# micro.net
KiCad netlist of a schematic drawn in Altium Designer
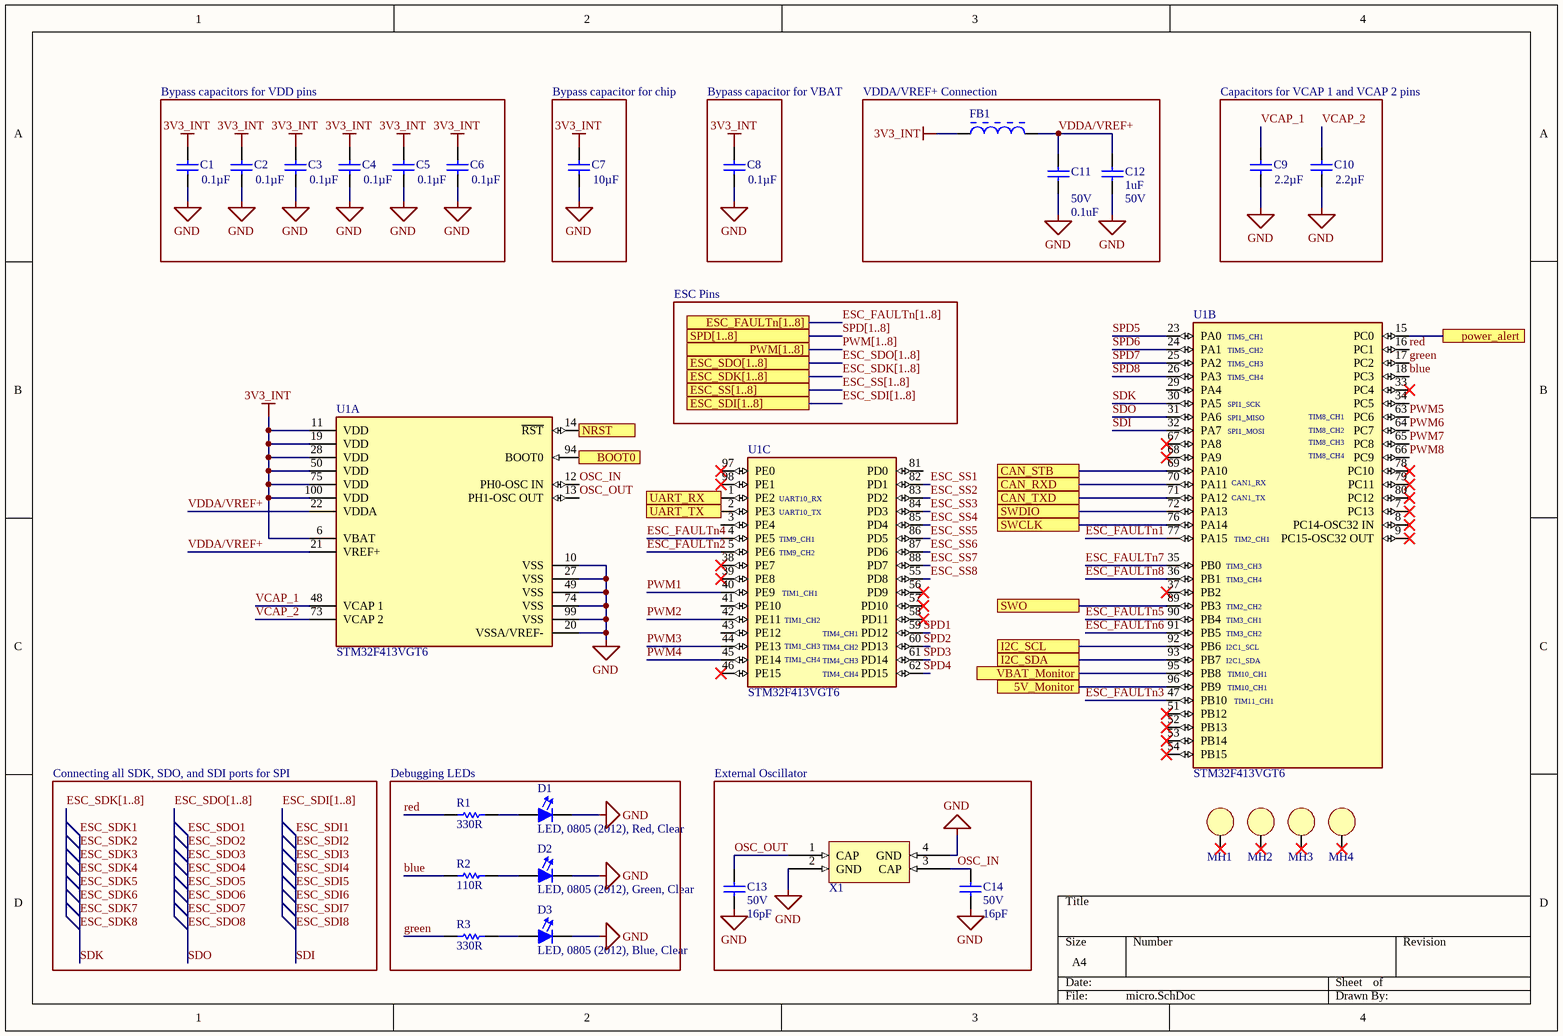
[diagram p0: micro.SchDoc]

(export (version "E")
  (design (tool "Eeschema 10.0.6"))
  (components
    (comp (ref "C1")
      (value "0.1µF")
      (footprint "CAPC1608N(0603\")")
      (description "Capacitor, Ceramic, 16V, +/- 10%, 0603 SMD, X7R")
      (fields
        (field (name "Comment") "0.1uF 16V 0603 SMD, Ceramic")
        (field (name "CREATED BY") "Andy Bates")
        (field (name "PUBLISHER") "AUVic")
      )
      (libsource (lib "") (part "Symbol_1"))
    )
    (comp (ref "C2")
      (value "0.1µF")
      (footprint "CAPC1608N(0603\")")
      (description "Capacitor, Ceramic, 16V, +/- 10%, 0603 SMD, X7R")
      (fields
        (field (name "Comment") "0.1uF 16V 0603 SMD, Ceramic")
        (field (name "CREATED BY") "Andy Bates")
        (field (name "PUBLISHER") "AUVic")
      )
      (libsource (lib "") (part "Symbol_1"))
    )
    (comp (ref "C3")
      (value "0.1µF")
      (footprint "CAPC1608N(0603\")")
      (description "Capacitor, Ceramic, 16V, +/- 10%, 0603 SMD, X7R")
      (fields
        (field (name "Comment") "0.1uF 16V 0603 SMD, Ceramic")
        (field (name "CREATED BY") "Andy Bates")
        (field (name "PUBLISHER") "AUVic")
      )
      (libsource (lib "") (part "Symbol_1"))
    )
    (comp (ref "C4")
      (value "0.1µF")
      (footprint "CAPC1608N(0603\")")
      (description "Capacitor, Ceramic, 16V, +/- 10%, 0603 SMD, X7R")
      (fields
        (field (name "Comment") "0.1uF 16V 0603 SMD, Ceramic")
        (field (name "CREATED BY") "Andy Bates")
        (field (name "PUBLISHER") "AUVic")
      )
      (libsource (lib "") (part "Symbol_1"))
    )
    (comp (ref "C5")
      (value "0.1µF")
      (footprint "CAPC1608N(0603\")")
      (description "Capacitor, Ceramic, 16V, +/- 10%, 0603 SMD, X7R")
      (fields
        (field (name "Comment") "0.1uF 16V 0603 SMD, Ceramic")
        (field (name "CREATED BY") "Andy Bates")
        (field (name "PUBLISHER") "AUVic")
      )
      (libsource (lib "") (part "Symbol_1"))
    )
    (comp (ref "C6")
      (value "0.1µF")
      (footprint "CAPC1608N(0603\")")
      (description "Capacitor, Ceramic, 16V, +/- 10%, 0603 SMD, X7R")
      (fields
        (field (name "Comment") "0.1uF 16V 0603 SMD, Ceramic")
        (field (name "CREATED BY") "Andy Bates")
        (field (name "PUBLISHER") "AUVic")
      )
      (libsource (lib "") (part "Symbol_1"))
    )
    (comp (ref "C7")
      (value "10µF")
      (footprint "CAPC2012N(0805\")")
      (description "Capacitor, Ceramic, 10V, +/- 10%, 0805 SMD, X5R")
      (fields
        (field (name "Comment") "10uF 10V 0805 SMD, Ceramic")
        (field (name "MADE BY") "Andy Bates")
        (field (name "PUBLISHER") "AUVic")
      )
      (libsource (lib "") (part "Symbol_3"))
    )
    (comp (ref "C8")
      (value "0.1µF")
      (footprint "CAPC1608N(0603\")")
      (description "Capacitor, Ceramic, 16V, +/- 10%, 0603 SMD, X7R")
      (fields
        (field (name "Comment") "0.1uF 16V 0603 SMD, Ceramic")
        (field (name "CREATED BY") "Andy Bates")
        (field (name "PUBLISHER") "AUVic")
      )
      (libsource (lib "") (part "Symbol_1"))
    )
    (comp (ref "C9")
      (value "2.2µF")
      (footprint "CAPC1608N(0603\")")
      (description "Capacitor, Ceramic, 50V, 10%, 0603 SMD, X5R")
      (fields
        (field (name "Comment") "2.2uF, 50V, 0603 SMD, X5R, Ceramic")
        (field (name "MADE BY") "*")
        (field (name "PUBLISHER") "AUVic")
      )
      (libsource (lib "") (part "Symbol_1"))
    )
    (comp (ref "C10")
      (value "2.2µF")
      (footprint "CAPC1608N(0603\")")
      (description "Capacitor, Ceramic, 50V, 10%, 0603 SMD, X5R")
      (fields
        (field (name "Comment") "2.2uF, 50V, 0603 SMD, X5R, Ceramic")
        (field (name "MADE BY") "*")
        (field (name "PUBLISHER") "AUVic")
      )
      (libsource (lib "") (part "Symbol_1"))
    )
    (comp (ref "C11")
      (value "CL10B104JB8NNNC")
      (footprint "FP-CL10-0_1-MFG")
      (description "CAP CER 0.1UF 50V X7R 0603")
      (fields
        (field (name "TOLERANCE") "5%")
        (field (name "VOLTAGE") "50V")
        (field (name "CAPACITANCE") "0.1uF")
      )
      (libsource (lib "AUVIC") (part "CAP-NP-2"))
    )
    (comp (ref "C12")
      (value "CL21B105KBFNNNG")
      (footprint "0803 CAP")
      (description "SAMSUNG ELECTRO-MECHANICS - CL21B105KBFNNNG - MLCC CAPACITORS")
      (fields
        (field (name "CAPACITANCE") "1uF")
        (field (name "TOLERANCE") "10%")
        (field (name "VOLTAGE") "50V")
      )
      (libsource (lib "") (part "Symbol_2"))
    )
    (comp (ref "C13")
      (value "16pF Ceramic 50V 5% 0603")
      (footprint "CAPC1608X90X35LL10T15")
      (description "Cap Ceramic 16pF 50V C0G 5% SMD 0603 125C Paper T/R")
      (fields
        (field (name "VOLTAGE") "50V")
        (field (name "TOLERANCE") "5%")
        (field (name "CAPACITANCE") "16pF")
      )
      (libsource (lib "AUVIC") (part "CAP"))
    )
    (comp (ref "C14")
      (value "16pF Ceramic 50V 5% 0603")
      (footprint "CAPC1608X90X35LL10T15")
      (description "Cap Ceramic 16pF 50V C0G 5% SMD 0603 125C Paper T/R")
      (fields
        (field (name "VOLTAGE") "50V")
        (field (name "TOLERANCE") "5%")
        (field (name "CAPACITANCE") "16pF")
      )
      (libsource (lib "AUVIC") (part "CAP"))
    )
    (comp (ref "D1")
      (value "LED, 0805 (2012), Red, Clear")
      (footprint "LED0805")
      (fields (field (name "CREATED BY") "Ashwin Sira"))
      (libsource (lib "AUVIC") (part "Symbol"))
    )
    (comp (ref "D2")
      (value "LED, 0805 (2012), Green, Clear")
      (footprint "LED0805")
      (fields (field (name "CREATED BY") "Andy Bates"))
      (libsource (lib "AUVIC") (part "Symbol"))
    )
    (comp (ref "D3")
      (value "LED, 0805 (2012), Blue, Clear")
      (footprint "LED0805")
      (fields (field (name "CREATED BY") "Ashwin Sira"))
      (libsource (lib "AUVIC") (part "Symbol"))
    )
    (comp (ref "FB1")
      (value "BLM18AG601SN1D")
      (footprint "MURA-BLM18-F-H1-CHIP-2_V")
      (fields (field (name "TOLERANCE") "25%"))
      (libsource (lib "AUVIC") (part "MURA-FB-2"))
    )
    (comp (ref "MH1")
      (value "Mount_Hole_3mm")
      (footprint "Mount-Hole_3mm")
      (description "Mounting hold for M3 hex standoff")
      (libsource (lib "AUVIC") (part "Mount_Hole_3mm"))
    )
    (comp (ref "MH2")
      (value "Mount_Hole_3mm")
      (footprint "Mount-Hole_3mm")
      (description "Mounting hold for M3 hex standoff")
      (libsource (lib "AUVIC") (part "Mount_Hole_3mm"))
    )
    (comp (ref "MH3")
      (value "Mount_Hole_3mm")
      (footprint "Mount-Hole_3mm")
      (description "Mounting hold for M3 hex standoff")
      (libsource (lib "AUVIC") (part "Mount_Hole_3mm"))
    )
    (comp (ref "MH4")
      (value "Mount_Hole_3mm")
      (footprint "Mount-Hole_3mm")
      (description "Mounting hold for M3 hex standoff")
      (libsource (lib "AUVIC") (part "Mount_Hole_3mm"))
    )
    (comp (ref "R1")
      (value "CRCW0603330RFKEA")
      (footprint "FP-CRCW0603-e3-IPC_C")
      (description "Res Thick Film 0603 330 Ohm 1% 0.1W(1/10W) +/-100ppm/ßC Pad SMD Automotive T/R")
      (fields (field (name "TOLERANCE") "1%") (field (name "RESISTANCE") "330R"))
      (libsource (lib "AUVIC") (part "RES"))
    )
    (comp (ref "R2")
      (value "RC0603FR-07110RL")
      (footprint "RESC1608X55X25ML10T15")
      (description "RES SMD 110 OHM 1% 1/10W 0603")
      (fields (field (name "TOLERANCE") "1%") (field (name "RESISTANCE") "110R"))
      (libsource (lib "AUVIC") (part "RES"))
    )
    (comp (ref "R3")
      (value "CRCW0603330RFKEA")
      (footprint "FP-CRCW0603-e3-IPC_C")
      (description "Res Thick Film 0603 330 Ohm 1% 0.1W(1/10W) +/-100ppm/ßC Pad SMD Automotive T/R")
      (fields (field (name "TOLERANCE") "1%") (field (name "RESISTANCE") "330R"))
      (libsource (lib "AUVIC") (part "RES"))
    )
    (comp (ref "U1")
      (value "STM32F413VGT6")
      (footprint "FP-LQFP100-1L-IPC_C")
      (description "IC MCU 32BIT 1MB FLASH 100LQFP")
      (libsource (lib "AUVIC") (part "38cd4fa6327843ddc5f699c16638a8b"))
    )
    (comp (ref "X1")
      (value "CRYSTAL 8.0MHZ 16PF SMD")
      (footprint "QFN250P750X520X140_HS-5M")
      (description "8MHz ±30ppm Crystal 16pF 80 Ohms 4-SMD, No Lead")
      (libsource (lib "AUVIC") (part "LFXTAL026380REEL"))
    )
  )
  (nets
    (net (code "1") (name "/5V_Monitor") (class "Default")
      (node (ref "U1") (pin "96") (pinfunction "PB9_96") (pintype "bidirectional"))
    )
    (net (code "2") (name "/BOOT0") (class "Default")
      (node (ref "U1") (pin "94") (pinfunction "BOOT0_94") (pintype "input"))
    )
    (net (code "3") (name "/CAN_RXD") (class "Default")
      (node (ref "U1") (pin "70") (pinfunction "PA11_70") (pintype "bidirectional"))
    )
    (net (code "4") (name "/CAN_STB") (class "Default")
      (node (ref "U1") (pin "69") (pinfunction "PA10_69") (pintype "bidirectional"))
    )
    (net (code "5") (name "/CAN_TXD") (class "Default")
      (node (ref "U1") (pin "71") (pinfunction "PA12_71") (pintype "bidirectional"))
    )
    (net (code "6") (name "/ESC_FAULTn1") (class "Default")
      (node (ref "U1") (pin "77") (pinfunction "PA15_77") (pintype "bidirectional"))
    )
    (net (code "7") (name "/ESC_FAULTn2") (class "Default")
      (node (ref "U1") (pin "5") (pinfunction "PE6_5") (pintype "bidirectional"))
    )
    (net (code "8") (name "/ESC_FAULTn3") (class "Default")
      (node (ref "U1") (pin "47") (pinfunction "PB10_47") (pintype "bidirectional"))
    )
    (net (code "9") (name "/ESC_FAULTn4") (class "Default")
      (node (ref "U1") (pin "4") (pinfunction "PE5_4") (pintype "bidirectional"))
    )
    (net (code "10") (name "/ESC_FAULTn5") (class "Default")
      (node (ref "U1") (pin "90") (pinfunction "PB4_90") (pintype "bidirectional"))
    )
    (net (code "11") (name "/ESC_FAULTn6") (class "Default")
      (node (ref "U1") (pin "91") (pinfunction "PB5_91") (pintype "bidirectional"))
    )
    (net (code "12") (name "/ESC_FAULTn7") (class "Default")
      (node (ref "U1") (pin "35") (pinfunction "PB0_35") (pintype "bidirectional"))
    )
    (net (code "13") (name "/ESC_FAULTn8") (class "Default")
      (node (ref "U1") (pin "36") (pinfunction "PB1_36") (pintype "bidirectional"))
    )
    (net (code "15") (name "/ESC_SDI8") (class "Default")
      (node (ref "U1") (pin "32") (pinfunction "PA7_32") (pintype "bidirectional"))
    )
    (net (code "17") (name "/ESC_SDK8") (class "Default")
      (node (ref "U1") (pin "30") (pinfunction "PA5_30") (pintype "bidirectional"))
    )
    (net (code "19") (name "/ESC_SDO8") (class "Default")
      (node (ref "U1") (pin "31") (pinfunction "PA6_31") (pintype "bidirectional"))
    )
    (net (code "21") (name "/ESC_SS1") (class "Default")
      (node (ref "U1") (pin "82") (pinfunction "PD1_82") (pintype "bidirectional"))
    )
    (net (code "22") (name "/ESC_SS2") (class "Default")
      (node (ref "U1") (pin "83") (pinfunction "PD2_83") (pintype "bidirectional"))
    )
    (net (code "23") (name "/ESC_SS3") (class "Default")
      (node (ref "U1") (pin "84") (pinfunction "PD3_84") (pintype "bidirectional"))
    )
    (net (code "24") (name "/ESC_SS4") (class "Default")
      (node (ref "U1") (pin "85") (pinfunction "PD4_85") (pintype "bidirectional"))
    )
    (net (code "25") (name "/ESC_SS5") (class "Default")
      (node (ref "U1") (pin "86") (pinfunction "PD5_86") (pintype "bidirectional"))
    )
    (net (code "26") (name "/ESC_SS6") (class "Default")
      (node (ref "U1") (pin "87") (pinfunction "PD6_87") (pintype "bidirectional"))
    )
    (net (code "27") (name "/ESC_SS7") (class "Default")
      (node (ref "U1") (pin "88") (pinfunction "PD7_88") (pintype "bidirectional"))
    )
    (net (code "28") (name "/ESC_SS8") (class "Default")
      (node (ref "U1") (pin "55") (pinfunction "PD8_55") (pintype "bidirectional"))
    )
    (net (code "30") (name "/I2C_SCL") (class "Default")
      (node (ref "U1") (pin "92") (pinfunction "PB6_92") (pintype "bidirectional"))
    )
    (net (code "31") (name "/I2C_SDA") (class "Default")
      (node (ref "U1") (pin "93") (pinfunction "PB7_93") (pintype "bidirectional"))
    )
    (net (code "32") (name "/NRST") (class "Default")
      (node (ref "U1") (pin "14") (pinfunction "~{RST}_14") (pintype "bidirectional"))
    )
    (net (code "33") (name "/OSC_IN") (class "Default")
      (node (ref "C14") (pin "2") (pinfunction "2_2") (pintype "passive"))
      (node (ref "U1") (pin "12") (pinfunction "PH0-OSC_IN_12") (pintype "bidirectional"))
      (node (ref "X1") (pin "3") (pinfunction "CAP_3") (pintype "input"))
    )
    (net (code "34") (name "/OSC_OUT") (class "Default")
      (node (ref "C13") (pin "2") (pinfunction "2_2") (pintype "passive"))
      (node (ref "U1") (pin "13") (pinfunction "PH1-OSC_OUT_13") (pintype "bidirectional"))
      (node (ref "X1") (pin "1") (pinfunction "CAP_1") (pintype "input"))
    )
    (net (code "35") (name "/PWM1") (class "Default")
      (node (ref "U1") (pin "40") (pinfunction "PE9_40") (pintype "bidirectional"))
    )
    (net (code "36") (name "/PWM2") (class "Default")
      (node (ref "U1") (pin "42") (pinfunction "PE11_42") (pintype "bidirectional"))
    )
    (net (code "37") (name "/PWM3") (class "Default")
      (node (ref "U1") (pin "44") (pinfunction "PE13_44") (pintype "bidirectional"))
    )
    (net (code "38") (name "/PWM4") (class "Default")
      (node (ref "U1") (pin "45") (pinfunction "PE14_45") (pintype "bidirectional"))
    )
    (net (code "39") (name "/PWM5") (class "Default")
      (node (ref "U1") (pin "63") (pinfunction "PC6_63") (pintype "bidirectional"))
    )
    (net (code "40") (name "/PWM6") (class "Default")
      (node (ref "U1") (pin "64") (pinfunction "PC7_64") (pintype "bidirectional"))
    )
    (net (code "41") (name "/PWM7") (class "Default")
      (node (ref "U1") (pin "65") (pinfunction "PC8_65") (pintype "bidirectional"))
    )
    (net (code "42") (name "/PWM8") (class "Default")
      (node (ref "U1") (pin "66") (pinfunction "PC9_66") (pintype "bidirectional"))
    )
    (net (code "44") (name "/SPD1") (class "Default")
      (node (ref "U1") (pin "59") (pinfunction "PD12_59") (pintype "bidirectional"))
    )
    (net (code "45") (name "/SPD2") (class "Default")
      (node (ref "U1") (pin "60") (pinfunction "PD13_60") (pintype "bidirectional"))
    )
    (net (code "46") (name "/SPD3") (class "Default")
      (node (ref "U1") (pin "61") (pinfunction "PD14_61") (pintype "bidirectional"))
    )
    (net (code "47") (name "/SPD4") (class "Default")
      (node (ref "U1") (pin "62") (pinfunction "PD15_62") (pintype "bidirectional"))
    )
    (net (code "48") (name "/SPD5") (class "Default")
      (node (ref "U1") (pin "23") (pinfunction "PA0_23") (pintype "bidirectional"))
    )
    (net (code "49") (name "/SPD6") (class "Default")
      (node (ref "U1") (pin "24") (pinfunction "PA1_24") (pintype "bidirectional"))
    )
    (net (code "50") (name "/SPD7") (class "Default")
      (node (ref "U1") (pin "25") (pinfunction "PA2_25") (pintype "bidirectional"))
    )
    (net (code "51") (name "/SPD8") (class "Default")
      (node (ref "U1") (pin "26") (pinfunction "PA3_26") (pintype "bidirectional"))
    )
    (net (code "53") (name "/SWCLK") (class "Default")
      (node (ref "U1") (pin "76") (pinfunction "PA14_76") (pintype "bidirectional"))
    )
    (net (code "54") (name "/SWDIO") (class "Default")
      (node (ref "U1") (pin "72") (pinfunction "PA13_72") (pintype "bidirectional"))
    )
    (net (code "55") (name "/SWO") (class "Default")
      (node (ref "U1") (pin "89") (pinfunction "PB3_89") (pintype "bidirectional"))
    )
    (net (code "56") (name "/UART_RX") (class "Default")
      (node (ref "U1") (pin "1") (pinfunction "PE2_1") (pintype "bidirectional"))
    )
    (net (code "57") (name "/UART_TX") (class "Default")
      (node (ref "U1") (pin "2") (pinfunction "PE3_2") (pintype "bidirectional"))
    )
    (net (code "58") (name "/VBAT_Monitor") (class "Default")
      (node (ref "U1") (pin "95") (pinfunction "PB8_95") (pintype "bidirectional"))
    )
    (net (code "59") (name "/VCAP_1") (class "Default")
      (node (ref "C9") (pin "2") (pinfunction "Cathode_2") (pintype "passive"))
      (node (ref "U1") (pin "48") (pinfunction "VCAP_1_48") (pintype "power_in"))
    )
    (net (code "60") (name "/VCAP_2") (class "Default")
      (node (ref "C10") (pin "2") (pinfunction "Cathode_2") (pintype "passive"))
      (node (ref "U1") (pin "73") (pinfunction "VCAP_2_73") (pintype "power_in"))
    )
    (net (code "61") (name "/VDDA{slash}VREF+") (class "Default")
      (node (ref "C11") (pin "1") (pinfunction "1_1") (pintype "passive"))
      (node (ref "C12") (pin "2") (pinfunction "2_2") (pintype "passive"))
      (node (ref "FB1") (pin "2") (pinfunction "2_2") (pintype "passive"))
      (node (ref "U1") (pin "21") (pinfunction "VREF+_21") (pintype "power_in"))
      (node (ref "U1") (pin "22") (pinfunction "VDDA_22") (pintype "power_in"))
    )
    (net (code "62") (name "/blue") (class "Default")
      (node (ref "R2") (pin "1") (pinfunction "1_1") (pintype "passive"))
      (node (ref "U1") (pin "18") (pinfunction "PC3_18") (pintype "bidirectional"))
    )
    (net (code "63") (name "/green") (class "Default")
      (node (ref "R3") (pin "1") (pinfunction "1_1") (pintype "passive"))
      (node (ref "U1") (pin "17") (pinfunction "PC2_17") (pintype "bidirectional"))
    )
    (net (code "64") (name "/power_alert") (class "Default")
      (node (ref "U1") (pin "15") (pinfunction "PC0_15") (pintype "bidirectional"))
    )
    (net (code "65") (name "/red") (class "Default")
      (node (ref "R1") (pin "1") (pinfunction "1_1") (pintype "passive"))
      (node (ref "U1") (pin "16") (pinfunction "PC1_16") (pintype "bidirectional"))
    )
    (net (code "66") (name "3V3_INT") (class "Default")
      (node (ref "C1") (pin "2") (pinfunction "Cathode_2") (pintype "passive"))
      (node (ref "C2") (pin "2") (pinfunction "Cathode_2") (pintype "passive"))
      (node (ref "C3") (pin "2") (pinfunction "Cathode_2") (pintype "passive"))
      (node (ref "C4") (pin "2") (pinfunction "Cathode_2") (pintype "passive"))
      (node (ref "C5") (pin "2") (pinfunction "Cathode_2") (pintype "passive"))
      (node (ref "C6") (pin "2") (pinfunction "Cathode_2") (pintype "passive"))
      (node (ref "C7") (pin "2") (pinfunction "Cathode_2") (pintype "passive"))
      (node (ref "C8") (pin "2") (pinfunction "Cathode_2") (pintype "passive"))
      (node (ref "FB1") (pin "1") (pinfunction "1_1") (pintype "passive"))
      (node (ref "U1") (pin "100") (pinfunction "VDD_100") (pintype "power_in"))
      (node (ref "U1") (pin "11") (pinfunction "VDD_11") (pintype "power_in"))
      (node (ref "U1") (pin "19") (pinfunction "VDD_19") (pintype "power_in"))
      (node (ref "U1") (pin "28") (pinfunction "VDD_28") (pintype "power_in"))
      (node (ref "U1") (pin "50") (pinfunction "VDD_50") (pintype "power_in"))
      (node (ref "U1") (pin "6") (pinfunction "VBAT_6") (pintype "power_in"))
      (node (ref "U1") (pin "75") (pinfunction "VDD_75") (pintype "power_in"))
    )
    (net (code "67") (name "GND") (class "Default")
      (node (ref "C1") (pin "1") (pinfunction "Anode_1") (pintype "passive"))
      (node (ref "C10") (pin "1") (pinfunction "Anode_1") (pintype "passive"))
      (node (ref "C11") (pin "2") (pinfunction "2_2") (pintype "passive"))
      (node (ref "C12") (pin "1") (pinfunction "1_1") (pintype "passive"))
      (node (ref "C13") (pin "1") (pinfunction "1_1") (pintype "passive"))
      (node (ref "C14") (pin "1") (pinfunction "1_1") (pintype "passive"))
      (node (ref "C2") (pin "1") (pinfunction "Anode_1") (pintype "passive"))
      (node (ref "C3") (pin "1") (pinfunction "Anode_1") (pintype "passive"))
      (node (ref "C4") (pin "1") (pinfunction "Anode_1") (pintype "passive"))
      (node (ref "C5") (pin "1") (pinfunction "Anode_1") (pintype "passive"))
      (node (ref "C6") (pin "1") (pinfunction "Anode_1") (pintype "passive"))
      (node (ref "C7") (pin "1") (pinfunction "Anode_1") (pintype "passive"))
      (node (ref "C8") (pin "1") (pinfunction "Anode_1") (pintype "passive"))
      (node (ref "C9") (pin "1") (pinfunction "Anode_1") (pintype "passive"))
      (node (ref "D1") (pin "1") (pinfunction "Cathode_1") (pintype "passive"))
      (node (ref "D2") (pin "1") (pinfunction "Cathode_1") (pintype "passive"))
      (node (ref "D3") (pin "1") (pinfunction "Cathode_1") (pintype "passive"))
      (node (ref "U1") (pin "10") (pinfunction "VSS_10") (pintype "power_in"))
      (node (ref "U1") (pin "20") (pinfunction "VSSA/VREF-_20") (pintype "power_in"))
      (node (ref "U1") (pin "27") (pinfunction "VSS_27") (pintype "power_in"))
      (node (ref "U1") (pin "49") (pinfunction "VSS_49") (pintype "power_in"))
      (node (ref "U1") (pin "74") (pinfunction "VSS_74") (pintype "power_in"))
      (node (ref "U1") (pin "99") (pinfunction "VSS_99") (pintype "power_in"))
      (node (ref "X1") (pin "2") (pinfunction "GND_2") (pintype "input"))
      (node (ref "X1") (pin "4") (pinfunction "GND_4") (pintype "input"))
    )
    (net (code "68") (name "Net-(D1-Anode)") (class "Default")
      (node (ref "D1") (pin "2") (pinfunction "Anode_2") (pintype "passive"))
      (node (ref "R1") (pin "2") (pinfunction "2_2") (pintype "passive"))
    )
    (net (code "69") (name "Net-(D2-Anode)") (class "Default")
      (node (ref "D2") (pin "2") (pinfunction "Anode_2") (pintype "passive"))
      (node (ref "R2") (pin "2") (pinfunction "2_2") (pintype "passive"))
    )
    (net (code "70") (name "Net-(D3-Anode)") (class "Default")
      (node (ref "D3") (pin "2") (pinfunction "Anode_2") (pintype "passive"))
      (node (ref "R3") (pin "2") (pinfunction "2_2") (pintype "passive"))
    )
    (net (code "71") (name "unconnected-(MH1-Pad1)") (class "Default")
      (node (ref "MH1") (pin "1") (pinfunction "1_1") (pintype "passive+no_connect"))
    )
    (net (code "72") (name "unconnected-(MH2-Pad1)") (class "Default")
      (node (ref "MH2") (pin "1") (pinfunction "1_1") (pintype "passive+no_connect"))
    )
    (net (code "73") (name "unconnected-(MH3-Pad1)") (class "Default")
      (node (ref "MH3") (pin "1") (pinfunction "1_1") (pintype "passive+no_connect"))
    )
    (net (code "74") (name "unconnected-(MH4-Pad1)") (class "Default")
      (node (ref "MH4") (pin "1") (pinfunction "1_1") (pintype "passive+no_connect"))
    )
    (net (code "75") (name "unconnected-(U1B-PA4-Pad29)") (class "Default")
      (node (ref "U1") (pin "29") (pinfunction "PA4_29") (pintype "bidirectional"))
    )
    (net (code "76") (name "unconnected-(U1B-PA8-Pad67)") (class "Default")
      (node (ref "U1") (pin "67") (pinfunction "PA8_67") (pintype "bidirectional+no_connect"))
    )
    (net (code "77") (name "unconnected-(U1B-PA9-Pad68)") (class "Default")
      (node (ref "U1") (pin "68") (pinfunction "PA9_68") (pintype "bidirectional+no_connect"))
    )
    (net (code "78") (name "unconnected-(U1B-PB2-Pad37)") (class "Default")
      (node (ref "U1") (pin "37") (pinfunction "PB2_37") (pintype "bidirectional+no_connect"))
    )
    (net (code "79") (name "unconnected-(U1B-PB12-Pad51)") (class "Default")
      (node (ref "U1") (pin "51") (pinfunction "PB12_51") (pintype "bidirectional+no_connect"))
    )
    (net (code "80") (name "unconnected-(U1B-PB13-Pad52)") (class "Default")
      (node (ref "U1") (pin "52") (pinfunction "PB13_52") (pintype "bidirectional+no_connect"))
    )
    (net (code "81") (name "unconnected-(U1B-PB14-Pad53)") (class "Default")
      (node (ref "U1") (pin "53") (pinfunction "PB14_53") (pintype "bidirectional+no_connect"))
    )
    (net (code "82") (name "unconnected-(U1B-PB15-Pad54)") (class "Default")
      (node (ref "U1") (pin "54") (pinfunction "PB15_54") (pintype "bidirectional+no_connect"))
    )
    (net (code "83") (name "unconnected-(U1B-PC4-Pad33)") (class "Default")
      (node (ref "U1") (pin "33") (pinfunction "PC4_33") (pintype "bidirectional+no_connect"))
    )
    (net (code "84") (name "unconnected-(U1B-PC5-Pad34)") (class "Default")
      (node (ref "U1") (pin "34") (pinfunction "PC5_34") (pintype "bidirectional"))
    )
    (net (code "85") (name "unconnected-(U1B-PC10-Pad78)") (class "Default")
      (node (ref "U1") (pin "78") (pinfunction "PC10_78") (pintype "bidirectional+no_connect"))
    )
    (net (code "86") (name "unconnected-(U1B-PC11-Pad79)") (class "Default")
      (node (ref "U1") (pin "79") (pinfunction "PC11_79") (pintype "bidirectional+no_connect"))
    )
    (net (code "87") (name "unconnected-(U1B-PC12-Pad80)") (class "Default")
      (node (ref "U1") (pin "80") (pinfunction "PC12_80") (pintype "bidirectional+no_connect"))
    )
    (net (code "88") (name "unconnected-(U1B-PC13-Pad7)") (class "Default")
      (node (ref "U1") (pin "7") (pinfunction "PC13_7") (pintype "bidirectional+no_connect"))
    )
    (net (code "89") (name "unconnected-(U1B-PC14-OSC32_IN-Pad8)") (class "Default")
      (node (ref "U1") (pin "8") (pinfunction "PC14-OSC32_IN_8") (pintype "bidirectional+no_connect"))
    )
    (net (code "90") (name "unconnected-(U1B-PC15-OSC32_OUT-Pad9)") (class "Default")
      (node (ref "U1") (pin "9") (pinfunction "PC15-OSC32_OUT_9") (pintype "bidirectional+no_connect"))
    )
    (net (code "91") (name "unconnected-(U1C-PD0-Pad81)") (class "Default")
      (node (ref "U1") (pin "81") (pinfunction "PD0_81") (pintype "bidirectional"))
    )
    (net (code "92") (name "unconnected-(U1C-PD9-Pad56)") (class "Default")
      (node (ref "U1") (pin "56") (pinfunction "PD9_56") (pintype "bidirectional+no_connect"))
    )
    (net (code "93") (name "unconnected-(U1C-PD10-Pad57)") (class "Default")
      (node (ref "U1") (pin "57") (pinfunction "PD10_57") (pintype "bidirectional+no_connect"))
    )
    (net (code "94") (name "unconnected-(U1C-PD11-Pad58)") (class "Default")
      (node (ref "U1") (pin "58") (pinfunction "PD11_58") (pintype "bidirectional+no_connect"))
    )
    (net (code "95") (name "unconnected-(U1C-PE0-Pad97)") (class "Default")
      (node (ref "U1") (pin "97") (pinfunction "PE0_97") (pintype "bidirectional+no_connect"))
    )
    (net (code "96") (name "unconnected-(U1C-PE1-Pad98)") (class "Default")
      (node (ref "U1") (pin "98") (pinfunction "PE1_98") (pintype "bidirectional+no_connect"))
    )
    (net (code "97") (name "unconnected-(U1C-PE4-Pad3)") (class "Default")
      (node (ref "U1") (pin "3") (pinfunction "PE4_3") (pintype "bidirectional"))
    )
    (net (code "98") (name "unconnected-(U1C-PE7-Pad38)") (class "Default")
      (node (ref "U1") (pin "38") (pinfunction "PE7_38") (pintype "bidirectional+no_connect"))
    )
    (net (code "99") (name "unconnected-(U1C-PE8-Pad39)") (class "Default")
      (node (ref "U1") (pin "39") (pinfunction "PE8_39") (pintype "bidirectional+no_connect"))
    )
    (net (code "100") (name "unconnected-(U1C-PE10-Pad41)") (class "Default")
      (node (ref "U1") (pin "41") (pinfunction "PE10_41") (pintype "bidirectional"))
    )
    (net (code "101") (name "unconnected-(U1C-PE12-Pad43)") (class "Default")
      (node (ref "U1") (pin "43") (pinfunction "PE12_43") (pintype "bidirectional"))
    )
    (net (code "102") (name "unconnected-(U1C-PE15-Pad46)") (class "Default")
      (node (ref "U1") (pin "46") (pinfunction "PE15_46") (pintype "bidirectional+no_connect"))
    )
  )
)
